# esp12_RGBWW.net
KiCad netlist of a schematic drawn in EAGLE
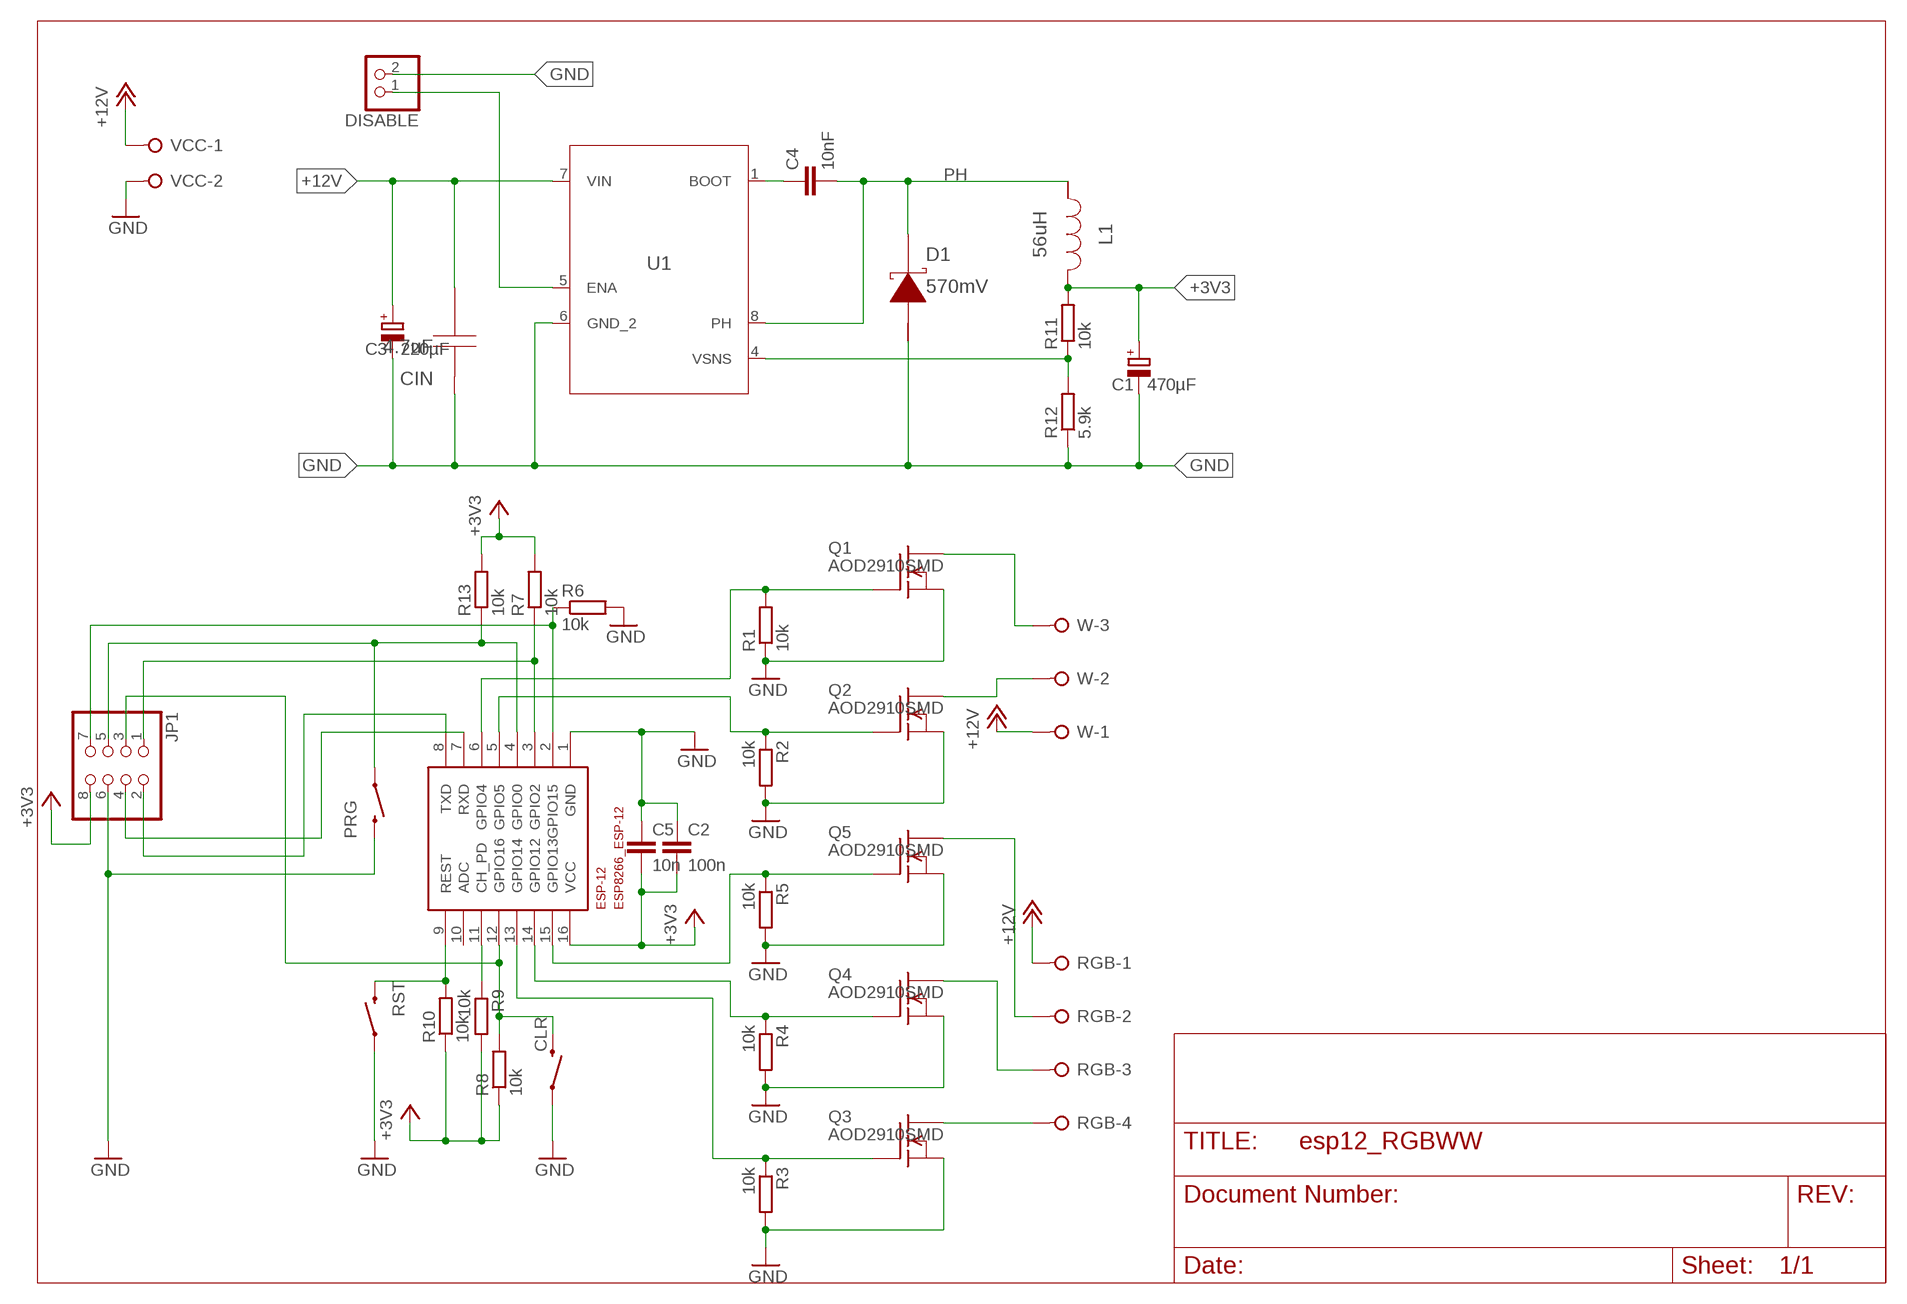
[diagram p0: schematic, sheet 1]

(export (version "E")
  (design (tool "Eeschema 10.0.6"))
  (components
    (comp (ref "C1")
      (value "470µF")
      (footprint "eagle-import:E2,5-7")
      (libsource (lib "eagle-import") (part "CPOL-EUE2.5-7"))
    )
    (comp (ref "C2")
      (value "100n")
      (footprint "eagle-import:C0805")
      (libsource (lib "eagle-import") (part "C-EUC0805"))
    )
    (comp (ref "C3")
      (value "220µF")
      (footprint "eagle-import:E2,5-7")
      (libsource (lib "eagle-import") (part "CPOL-EUE2.5-7"))
    )
    (comp (ref "C4")
      (value "10nF")
      (footprint "eagle-import:C0805")
      (libsource (lib "eagle-import") (part "resistor_C-EUC0805"))
    )
    (comp (ref "C5")
      (value "10n")
      (footprint "eagle-import:C0805")
      (libsource (lib "eagle-import") (part "C-EUC0805"))
    )
    (comp (ref "CIN")
      (value "4.7uF")
      (footprint "eagle-import:1206")
      (fields (field (name "MANUFACTURER_PART_NUMBER") "GRM31CR71H475KA12L"))
      (libsource (lib "eagle-import") (part "GRM31CR71H475KA12L"))
    )
    (comp (ref "CLR")
      (value "SWITCH-MOMENTARY-2SMD-1101NE")
      (footprint "eagle-import:TACTILE-SWITCH-1101NE")
      (libsource (lib "eagle-import") (part "SWITCH-MOMENTARY-2SMD-1101NE"))
    )
    (comp (ref "D1")
      (value "570mV")
      (footprint "eagle-import:SMA")
      (fields (field (name "MANUFACTURER_PART_NUMBER") "B16013F"))
      (libsource (lib "eagle-import") (part "B160-13-F"))
    )
    (comp (ref "DISABLE")
      (value "PINHD-1X2")
      (footprint "eagle-import:1X02")
      (libsource (lib "eagle-import") (part "PINHD-1X2"))
    )
    (comp (ref "ESP-12")
      (value "ESP8266_ESP-12")
      (footprint "eagle-import:ESP8266-ESP12")
      (libsource (lib "eagle-import") (part "ESP8266_ESP-12"))
    )
    (comp (ref "JP1")
      (value "PINHD-2X4")
      (footprint "eagle-import:2X04")
      (libsource (lib "eagle-import") (part "PINHD-2X4"))
    )
    (comp (ref "L1")
      (value "56uH")
      (footprint "eagle-import:IND_NPI75C")
      (fields (field (name "MANUFACTURER_PART_NUMBER") "NPI75C560KTRF"))
      (libsource (lib "eagle-import") (part "NPI75C560KTRF"))
    )
    (comp (ref "PRG")
      (value "SWITCH-MOMENTARY-2SMD-1101NE")
      (footprint "eagle-import:TACTILE-SWITCH-1101NE")
      (libsource (lib "eagle-import") (part "SWITCH-MOMENTARY-2SMD-1101NE"))
    )
    (comp (ref "Q1")
      (value "AOD2910SMD")
      (footprint "eagle-import:DPAK-3")
      (libsource (lib "eagle-import") (part "AOD2910SMD"))
    )
    (comp (ref "Q2")
      (value "AOD2910SMD")
      (footprint "eagle-import:DPAK-3")
      (libsource (lib "eagle-import") (part "AOD2910SMD"))
    )
    (comp (ref "Q3")
      (value "AOD2910SMD")
      (footprint "eagle-import:DPAK-3")
      (libsource (lib "eagle-import") (part "AOD2910SMD"))
    )
    (comp (ref "Q4")
      (value "AOD2910SMD")
      (footprint "eagle-import:DPAK-3")
      (libsource (lib "eagle-import") (part "AOD2910SMD"))
    )
    (comp (ref "Q5")
      (value "AOD2910SMD")
      (footprint "eagle-import:DPAK-3")
      (libsource (lib "eagle-import") (part "AOD2910SMD"))
    )
    (comp (ref "R1")
      (value "10k")
      (footprint "eagle-import:R0805")
      (libsource (lib "eagle-import") (part "R-EU_R0805"))
    )
    (comp (ref "R2")
      (value "10k")
      (footprint "eagle-import:R0805")
      (libsource (lib "eagle-import") (part "R-EU_R0805"))
    )
    (comp (ref "R3")
      (value "10k")
      (footprint "eagle-import:R0805")
      (libsource (lib "eagle-import") (part "R-EU_R0805"))
    )
    (comp (ref "R4")
      (value "10k")
      (footprint "eagle-import:R0805")
      (libsource (lib "eagle-import") (part "R-EU_R0805"))
    )
    (comp (ref "R5")
      (value "10k")
      (footprint "eagle-import:R0805")
      (libsource (lib "eagle-import") (part "R-EU_R0805"))
    )
    (comp (ref "R6")
      (value "10k")
      (footprint "eagle-import:R0805")
      (libsource (lib "eagle-import") (part "R-EU_R0805"))
    )
    (comp (ref "R7")
      (value "10k")
      (footprint "eagle-import:R0805")
      (libsource (lib "eagle-import") (part "R-EU_R0805"))
    )
    (comp (ref "R8")
      (value "10k")
      (footprint "eagle-import:R0805")
      (libsource (lib "eagle-import") (part "R-EU_R0805"))
    )
    (comp (ref "R9")
      (value "10k")
      (footprint "eagle-import:R0805")
      (libsource (lib "eagle-import") (part "R-EU_R0805"))
    )
    (comp (ref "R10")
      (value "10k")
      (footprint "eagle-import:R0805")
      (libsource (lib "eagle-import") (part "R-EU_R0805"))
    )
    (comp (ref "R11")
      (value "10k")
      (footprint "eagle-import:R0805")
      (libsource (lib "eagle-import") (part "resistor_R-EU_R0805"))
    )
    (comp (ref "R12")
      (value "5.9k")
      (footprint "eagle-import:R0805")
      (libsource (lib "eagle-import") (part "resistor_R-EU_R0805"))
    )
    (comp (ref "R13")
      (value "10k")
      (footprint "eagle-import:R0805")
      (libsource (lib "eagle-import") (part "R-EU_R0805"))
    )
    (comp (ref "RGB")
      (value "W237-04P")
      (footprint "eagle-import:W237-4P")
      (libsource (lib "eagle-import") (part "W237-04P"))
    )
    (comp (ref "RST")
      (value "SWITCH-MOMENTARY-2SMD-1101NE")
      (footprint "eagle-import:TACTILE-SWITCH-1101NE")
      (libsource (lib "eagle-import") (part "SWITCH-MOMENTARY-2SMD-1101NE"))
    )
    (comp (ref "U1")
      (value "TPS5410DR")
      (footprint "eagle-import:M08A")
      (libsource (lib "eagle-import") (part "TPS5410DR"))
    )
    (comp (ref "VCC")
      (value "W237-02P")
      (footprint "eagle-import:W237-132")
      (libsource (lib "eagle-import") (part "W237-02P"))
    )
    (comp (ref "W")
      (value "W237-03P")
      (footprint "eagle-import:W237-133")
      (libsource (lib "eagle-import") (part "W237-03P"))
    )
  )
  (nets
    (net (code "1") (name "+3V3") (class "Default")
      (node (ref "C1") (pin "+") (pinfunction "+_+") (pintype "passive"))
      (node (ref "C2") (pin "2") (pinfunction "2_2") (pintype "passive"))
      (node (ref "C5") (pin "2") (pinfunction "2_2") (pintype "passive"))
      (node (ref "ESP-12") (pin "16") (pinfunction "VCC_16") (pintype "bidirectional"))
      (node (ref "JP1") (pin "8") (pinfunction "8_8") (pintype "passive"))
      (node (ref "L1") (pin "1") (pinfunction "1_1") (pintype "passive"))
      (node (ref "R10") (pin "1") (pinfunction "1_1") (pintype "passive"))
      (node (ref "R11") (pin "2") (pinfunction "2_2") (pintype "passive"))
      (node (ref "R13") (pin "2") (pinfunction "2_2") (pintype "passive"))
      (node (ref "R7") (pin "2") (pinfunction "2_2") (pintype "passive"))
      (node (ref "R8") (pin "1") (pinfunction "1_1") (pintype "passive"))
      (node (ref "R9") (pin "2") (pinfunction "2_2") (pintype "passive"))
    )
    (net (code "2") (name "+12V") (class "Default")
      (node (ref "C3") (pin "+") (pinfunction "+_+") (pintype "passive"))
      (node (ref "CIN") (pin "2") (pinfunction "2_2") (pintype "passive"))
      (node (ref "RGB") (pin "1") (pinfunction "KL_1") (pintype "passive"))
      (node (ref "U1") (pin "7") (pinfunction "VIN_7") (pintype "passive"))
      (node (ref "VCC") (pin "1") (pinfunction "KL_1") (pintype "passive"))
      (node (ref "W") (pin "1") (pinfunction "KL_1") (pintype "passive"))
    )
    (net (code "3") (name "/PH") (class "Default")
      (node (ref "C4") (pin "2") (pinfunction "2_2") (pintype "passive"))
      (node (ref "D1") (pin "1") (pinfunction "K_1") (pintype "passive"))
      (node (ref "L1") (pin "2") (pinfunction "2_2") (pintype "passive"))
      (node (ref "U1") (pin "8") (pinfunction "PH_8") (pintype "passive"))
    )
    (net (code "4") (name "GND") (class "Default")
      (node (ref "C1") (pin "-") (pinfunction "-_-") (pintype "passive"))
      (node (ref "C2") (pin "1") (pinfunction "1_1") (pintype "passive"))
      (node (ref "C3") (pin "-") (pinfunction "-_-") (pintype "passive"))
      (node (ref "C5") (pin "1") (pinfunction "1_1") (pintype "passive"))
      (node (ref "CIN") (pin "1") (pinfunction "1_1") (pintype "passive"))
      (node (ref "CLR") (pin "1") (pinfunction "1_1") (pintype "passive"))
      (node (ref "D1") (pin "2") (pinfunction "A_2") (pintype "passive"))
      (node (ref "DISABLE") (pin "2") (pinfunction "2_2") (pintype "passive"))
      (node (ref "ESP-12") (pin "1") (pinfunction "GND_1") (pintype "bidirectional"))
      (node (ref "JP1") (pin "6") (pinfunction "6_6") (pintype "passive"))
      (node (ref "PRG") (pin "2") (pinfunction "2_2") (pintype "passive"))
      (node (ref "Q1") (pin "3") (pinfunction "S_3") (pintype "passive"))
      (node (ref "Q2") (pin "3") (pinfunction "S_3") (pintype "passive"))
      (node (ref "Q3") (pin "3") (pinfunction "S_3") (pintype "passive"))
      (node (ref "Q4") (pin "3") (pinfunction "S_3") (pintype "passive"))
      (node (ref "Q5") (pin "3") (pinfunction "S_3") (pintype "passive"))
      (node (ref "R1") (pin "1") (pinfunction "1_1") (pintype "passive"))
      (node (ref "R12") (pin "1") (pinfunction "1_1") (pintype "passive"))
      (node (ref "R2") (pin "2") (pinfunction "2_2") (pintype "passive"))
      (node (ref "R3") (pin "2") (pinfunction "2_2") (pintype "passive"))
      (node (ref "R4") (pin "2") (pinfunction "2_2") (pintype "passive"))
      (node (ref "R5") (pin "2") (pinfunction "2_2") (pintype "passive"))
      (node (ref "R6") (pin "2") (pinfunction "2_2") (pintype "passive"))
      (node (ref "RST") (pin "1") (pinfunction "1_1") (pintype "passive"))
      (node (ref "U1") (pin "6") (pinfunction "GND_2_6") (pintype "passive"))
      (node (ref "VCC") (pin "2") (pinfunction "KL_2") (pintype "passive"))
    )
    (net (code "5") (name "Net-(ESP-12-CH_PD)") (class "Default")
      (node (ref "ESP-12") (pin "11") (pinfunction "CH_PD_11") (pintype "bidirectional"))
      (node (ref "R9") (pin "1") (pinfunction "1_1") (pintype "passive"))
    )
    (net (code "6") (name "Net-(ESP-12-GPIO0)") (class "Default")
      (node (ref "ESP-12") (pin "4") (pinfunction "GPIO0_4") (pintype "bidirectional"))
      (node (ref "JP1") (pin "5") (pinfunction "5_5") (pintype "passive"))
      (node (ref "PRG") (pin "1") (pinfunction "1_1") (pintype "passive"))
      (node (ref "R13") (pin "1") (pinfunction "1_1") (pintype "passive"))
    )
    (net (code "7") (name "Net-(ESP-12-GPIO2)") (class "Default")
      (node (ref "ESP-12") (pin "3") (pinfunction "GPIO2_3") (pintype "bidirectional"))
      (node (ref "JP1") (pin "1") (pinfunction "1_1") (pintype "passive"))
      (node (ref "R7") (pin "1") (pinfunction "1_1") (pintype "passive"))
    )
    (net (code "8") (name "Net-(ESP-12-GPIO4)") (class "Default")
      (node (ref "ESP-12") (pin "6") (pinfunction "GPIO4_6") (pintype "bidirectional"))
      (node (ref "Q1") (pin "1") (pinfunction "G_1") (pintype "passive"))
      (node (ref "R1") (pin "2") (pinfunction "2_2") (pintype "passive"))
    )
    (net (code "9") (name "Net-(ESP-12-GPIO5)") (class "Default")
      (node (ref "ESP-12") (pin "5") (pinfunction "GPIO5_5") (pintype "bidirectional"))
      (node (ref "Q2") (pin "1") (pinfunction "G_1") (pintype "passive"))
      (node (ref "R2") (pin "1") (pinfunction "1_1") (pintype "passive"))
    )
    (net (code "10") (name "Net-(ESP-12-GPIO12)") (class "Default")
      (node (ref "ESP-12") (pin "14") (pinfunction "GPIO12_14") (pintype "bidirectional"))
      (node (ref "Q4") (pin "1") (pinfunction "G_1") (pintype "passive"))
      (node (ref "R4") (pin "1") (pinfunction "1_1") (pintype "passive"))
    )
    (net (code "11") (name "Net-(ESP-12-GPIO13)") (class "Default")
      (node (ref "ESP-12") (pin "15") (pinfunction "GPIO13_15") (pintype "bidirectional"))
      (node (ref "Q5") (pin "1") (pinfunction "G_1") (pintype "passive"))
      (node (ref "R5") (pin "1") (pinfunction "1_1") (pintype "passive"))
    )
    (net (code "12") (name "Net-(ESP-12-GPIO14)") (class "Default")
      (node (ref "ESP-12") (pin "13") (pinfunction "GPIO14_13") (pintype "bidirectional"))
      (node (ref "Q3") (pin "1") (pinfunction "G_1") (pintype "passive"))
      (node (ref "R3") (pin "1") (pinfunction "1_1") (pintype "passive"))
    )
    (net (code "13") (name "Net-(ESP-12-GPIO15)") (class "Default")
      (node (ref "ESP-12") (pin "2") (pinfunction "GPIO15_2") (pintype "bidirectional"))
      (node (ref "JP1") (pin "7") (pinfunction "7_7") (pintype "passive"))
      (node (ref "R6") (pin "1") (pinfunction "1_1") (pintype "passive"))
    )
    (net (code "14") (name "Net-(ESP-12-GPIO16)") (class "Default")
      (node (ref "CLR") (pin "2") (pinfunction "2_2") (pintype "passive"))
      (node (ref "ESP-12") (pin "12") (pinfunction "GPIO16_12") (pintype "bidirectional"))
      (node (ref "JP1") (pin "3") (pinfunction "3_3") (pintype "passive"))
      (node (ref "R8") (pin "2") (pinfunction "2_2") (pintype "passive"))
    )
    (net (code "15") (name "Net-(ESP-12-REST)") (class "Default")
      (node (ref "ESP-12") (pin "9") (pinfunction "REST_9") (pintype "bidirectional"))
      (node (ref "R10") (pin "2") (pinfunction "2_2") (pintype "passive"))
      (node (ref "RST") (pin "2") (pinfunction "2_2") (pintype "passive"))
    )
    (net (code "16") (name "Net-(ESP-12-RXD)") (class "Default")
      (node (ref "ESP-12") (pin "7") (pinfunction "RXD_7") (pintype "bidirectional"))
      (node (ref "JP1") (pin "4") (pinfunction "4_4") (pintype "passive"))
    )
    (net (code "17") (name "Net-(ESP-12-TXD)") (class "Default")
      (node (ref "ESP-12") (pin "8") (pinfunction "TXD_8") (pintype "bidirectional"))
      (node (ref "JP1") (pin "2") (pinfunction "2_2") (pintype "passive"))
    )
    (net (code "18") (name "Net-(Q1-D)") (class "Default")
      (node (ref "Q1") (pin "4") (pinfunction "D_4") (pintype "passive"))
      (node (ref "W") (pin "3") (pinfunction "KL_3") (pintype "passive"))
    )
    (net (code "19") (name "Net-(Q2-D)") (class "Default")
      (node (ref "Q2") (pin "4") (pinfunction "D_4") (pintype "passive"))
      (node (ref "W") (pin "2") (pinfunction "KL_2") (pintype "passive"))
    )
    (net (code "20") (name "Net-(Q3-D)") (class "Default")
      (node (ref "Q3") (pin "4") (pinfunction "D_4") (pintype "passive"))
      (node (ref "RGB") (pin "4") (pinfunction "KL_4") (pintype "passive"))
    )
    (net (code "21") (name "Net-(Q4-D)") (class "Default")
      (node (ref "Q4") (pin "4") (pinfunction "D_4") (pintype "passive"))
      (node (ref "RGB") (pin "3") (pinfunction "KL_3") (pintype "passive"))
    )
    (net (code "22") (name "Net-(Q5-D)") (class "Default")
      (node (ref "Q5") (pin "4") (pinfunction "D_4") (pintype "passive"))
      (node (ref "RGB") (pin "2") (pinfunction "KL_2") (pintype "passive"))
    )
    (net (code "23") (name "Net-(U1-BOOT)") (class "Default")
      (node (ref "C4") (pin "1") (pinfunction "1_1") (pintype "passive"))
      (node (ref "U1") (pin "1") (pinfunction "BOOT_1") (pintype "passive"))
    )
    (net (code "24") (name "Net-(U1-ENA)") (class "Default")
      (node (ref "DISABLE") (pin "1") (pinfunction "1_1") (pintype "passive"))
      (node (ref "U1") (pin "5") (pinfunction "ENA_5") (pintype "passive"))
    )
    (net (code "25") (name "Net-(U1-VSNS)") (class "Default")
      (node (ref "R11") (pin "1") (pinfunction "1_1") (pintype "passive"))
      (node (ref "R12") (pin "2") (pinfunction "2_2") (pintype "passive"))
      (node (ref "U1") (pin "4") (pinfunction "VSNS_4") (pintype "passive"))
    )
    (net (code "26") (name "unconnected-(ESP-12-ADC-Pad10)") (class "Default")
      (node (ref "ESP-12") (pin "10") (pinfunction "ADC_10") (pintype "bidirectional"))
    )
  )
)
